# SNES.net
KiCad netlist of a schematic drawn in EAGLE
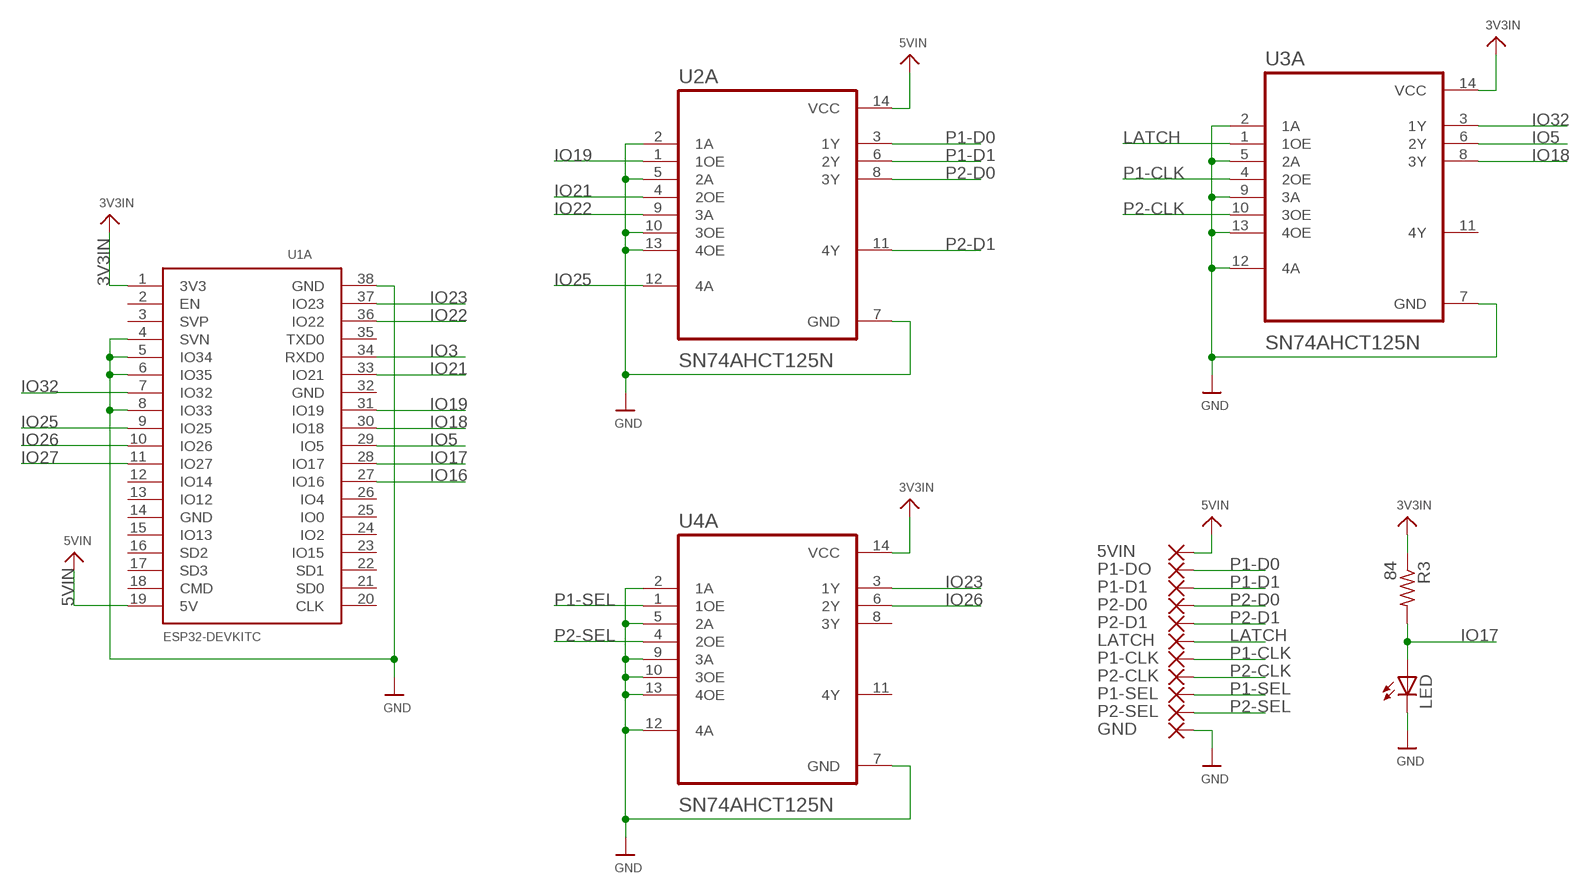
[diagram p0: schematic, sheet 1]

(export (version "E")
  (design (tool "Eeschema 10.0.6"))
  (components
    (comp (ref "5VIN")
      (value "SMD5")
      (footprint "eagle-import:SMD2,54-5,08")
      (libsource (lib "eagle-import") (part "SMD5"))
    )
    (comp (ref "GND")
      (value "SMD5")
      (footprint "eagle-import:SMD2,54-5,08")
      (libsource (lib "eagle-import") (part "SMD5"))
    )
    (comp (ref "LATCH")
      (value "SMD5")
      (footprint "eagle-import:SMD2,54-5,08")
      (libsource (lib "eagle-import") (part "SMD5"))
    )
    (comp (ref "LED")
      (value "LEDCHIPLED_1206")
      (footprint "eagle-import:CHIPLED_1206")
      (libsource (lib "eagle-import") (part "LEDCHIPLED_1206"))
    )
    (comp (ref "P1-CLK")
      (value "SMD5")
      (footprint "eagle-import:SMD2,54-5,08")
      (libsource (lib "eagle-import") (part "SMD5"))
    )
    (comp (ref "P1-D1")
      (value "SMD5")
      (footprint "eagle-import:SMD2,54-5,08")
      (libsource (lib "eagle-import") (part "SMD5"))
    )
    (comp (ref "P1-DO")
      (value "SMD5")
      (footprint "eagle-import:SMD2,54-5,08")
      (libsource (lib "eagle-import") (part "SMD5"))
    )
    (comp (ref "P1-SEL")
      (value "SMD5")
      (footprint "eagle-import:SMD2,54-5,08")
      (libsource (lib "eagle-import") (part "SMD5"))
    )
    (comp (ref "P2-CLK")
      (value "SMD5")
      (footprint "eagle-import:SMD2,54-5,08")
      (libsource (lib "eagle-import") (part "SMD5"))
    )
    (comp (ref "P2-D0")
      (value "SMD5")
      (footprint "eagle-import:SMD2,54-5,08")
      (libsource (lib "eagle-import") (part "SMD5"))
    )
    (comp (ref "P2-D1")
      (value "SMD5")
      (footprint "eagle-import:SMD2,54-5,08")
      (libsource (lib "eagle-import") (part "SMD5"))
    )
    (comp (ref "P2-SEL")
      (value "SMD5")
      (footprint "eagle-import:SMD2,54-5,08")
      (libsource (lib "eagle-import") (part "SMD5"))
    )
    (comp (ref "R3")
      (value "84")
      (footprint "eagle-import:R1206")
      (libsource (lib "eagle-import") (part "R-US_R1206"))
    )
    (comp (ref "U1A")
      (value "ESP32DEVKITC")
      (footprint "eagle-import:ESP32-DEVKITC")
      (libsource (lib "eagle-import") (part "ESP32DEVKITC"))
    )
    (comp (ref "U2A")
      (value "SN74AHCT125N")
      (footprint "eagle-import:DIP794W45P254L1969H508Q14")
      (fields (field (name "MF") "Texas Instruments"))
      (libsource (lib "eagle-import") (part "SN74AHCT125N"))
    )
    (comp (ref "U3A")
      (value "SN74AHCT125N")
      (footprint "eagle-import:DIP794W45P254L1969H508Q14")
      (fields (field (name "MF") "Texas Instruments"))
      (libsource (lib "eagle-import") (part "SN74AHCT125N"))
    )
    (comp (ref "U4A")
      (value "SN74AHCT125N")
      (footprint "eagle-import:DIP794W45P254L1969H508Q14")
      (fields (field (name "MF") "Texas Instruments"))
      (libsource (lib "eagle-import") (part "SN74AHCT125N"))
    )
  )
  (nets
    (net (code "1") (name "/IO3") (class "Default")
      (node (ref "U1A") (pin "34") (pinfunction "RXD0_34") (pintype "bidirectional"))
    )
    (net (code "2") (name "/IO5") (class "Default")
      (node (ref "U1A") (pin "29") (pinfunction "IO5_29") (pintype "bidirectional"))
      (node (ref "U3A") (pin "6") (pinfunction "2Y_6") (pintype "output"))
    )
    (net (code "3") (name "/IO16") (class "Default")
      (node (ref "U1A") (pin "27") (pinfunction "IO16_27") (pintype "bidirectional"))
    )
    (net (code "4") (name "/IO17") (class "Default")
      (node (ref "LED") (pin "A") (pinfunction "A_A") (pintype "passive"))
      (node (ref "R3") (pin "2") (pinfunction "2_2") (pintype "passive"))
      (node (ref "U1A") (pin "28") (pinfunction "IO17_28") (pintype "bidirectional"))
    )
    (net (code "5") (name "/IO18") (class "Default")
      (node (ref "U1A") (pin "30") (pinfunction "IO18_30") (pintype "bidirectional"))
      (node (ref "U3A") (pin "8") (pinfunction "3Y_8") (pintype "output"))
    )
    (net (code "6") (name "/IO19") (class "Default")
      (node (ref "U1A") (pin "31") (pinfunction "IO19_31") (pintype "bidirectional"))
      (node (ref "U2A") (pin "1") (pinfunction "1OE_1") (pintype "input"))
    )
    (net (code "7") (name "/IO21") (class "Default")
      (node (ref "U1A") (pin "33") (pinfunction "IO21_33") (pintype "bidirectional"))
      (node (ref "U2A") (pin "4") (pinfunction "2OE_4") (pintype "input"))
    )
    (net (code "8") (name "/IO22") (class "Default")
      (node (ref "U1A") (pin "36") (pinfunction "IO22_36") (pintype "bidirectional"))
      (node (ref "U2A") (pin "9") (pinfunction "3A_9") (pintype "input"))
    )
    (net (code "9") (name "/IO23") (class "Default")
      (node (ref "U1A") (pin "37") (pinfunction "IO23_37") (pintype "bidirectional"))
      (node (ref "U4A") (pin "3") (pinfunction "1Y_3") (pintype "output"))
    )
    (net (code "10") (name "/IO25") (class "Default")
      (node (ref "U1A") (pin "9") (pinfunction "IO25_9") (pintype "bidirectional"))
      (node (ref "U2A") (pin "12") (pinfunction "4A_12") (pintype "bidirectional"))
    )
    (net (code "11") (name "/IO26") (class "Default")
      (node (ref "U1A") (pin "10") (pinfunction "IO26_10") (pintype "bidirectional"))
      (node (ref "U4A") (pin "6") (pinfunction "2Y_6") (pintype "output"))
    )
    (net (code "12") (name "/IO27") (class "Default")
      (node (ref "U1A") (pin "11") (pinfunction "IO27_11") (pintype "bidirectional"))
    )
    (net (code "13") (name "/IO32") (class "Default")
      (node (ref "U1A") (pin "7") (pinfunction "IO32_7") (pintype "bidirectional"))
      (node (ref "U3A") (pin "3") (pinfunction "1Y_3") (pintype "output"))
    )
    (net (code "14") (name "/LATCH") (class "Default")
      (node (ref "LATCH") (pin "1") (pinfunction "P_1") (pintype "passive"))
      (node (ref "U3A") (pin "1") (pinfunction "1OE_1") (pintype "input"))
    )
    (net (code "15") (name "/P1-CLK") (class "Default")
      (node (ref "P1-CLK") (pin "1") (pinfunction "P_1") (pintype "passive"))
      (node (ref "U3A") (pin "4") (pinfunction "2OE_4") (pintype "input"))
    )
    (net (code "16") (name "/P1-D0") (class "Default")
      (node (ref "P1-DO") (pin "1") (pinfunction "P_1") (pintype "passive"))
      (node (ref "U2A") (pin "3") (pinfunction "1Y_3") (pintype "output"))
    )
    (net (code "17") (name "/P1-D1") (class "Default")
      (node (ref "P1-D1") (pin "1") (pinfunction "P_1") (pintype "passive"))
      (node (ref "U2A") (pin "6") (pinfunction "2Y_6") (pintype "output"))
    )
    (net (code "18") (name "/P1-SEL") (class "Default")
      (node (ref "P1-SEL") (pin "1") (pinfunction "P_1") (pintype "passive"))
      (node (ref "U4A") (pin "1") (pinfunction "1OE_1") (pintype "input"))
    )
    (net (code "19") (name "/P2-CLK") (class "Default")
      (node (ref "P2-CLK") (pin "1") (pinfunction "P_1") (pintype "passive"))
      (node (ref "U3A") (pin "10") (pinfunction "3OE_10") (pintype "input"))
    )
    (net (code "20") (name "/P2-D0") (class "Default")
      (node (ref "P2-D0") (pin "1") (pinfunction "P_1") (pintype "passive"))
      (node (ref "U2A") (pin "8") (pinfunction "3Y_8") (pintype "output"))
    )
    (net (code "21") (name "/P2-D1") (class "Default")
      (node (ref "P2-D1") (pin "1") (pinfunction "P_1") (pintype "passive"))
      (node (ref "U2A") (pin "11") (pinfunction "4Y_11") (pintype "output"))
    )
    (net (code "22") (name "/P2-SEL") (class "Default")
      (node (ref "P2-SEL") (pin "1") (pinfunction "P_1") (pintype "passive"))
      (node (ref "U4A") (pin "4") (pinfunction "2OE_4") (pintype "input"))
    )
    (net (code "23") (name "3V3IN") (class "Default")
      (node (ref "R3") (pin "1") (pinfunction "1_1") (pintype "passive"))
      (node (ref "U1A") (pin "1") (pinfunction "3V3_1") (pintype "bidirectional"))
      (node (ref "U3A") (pin "14") (pinfunction "VCC_14") (pintype "power_in"))
      (node (ref "U4A") (pin "14") (pinfunction "VCC_14") (pintype "power_in"))
    )
    (net (code "24") (name "5VIN") (class "Default")
      (node (ref "5VIN") (pin "1") (pinfunction "P_1") (pintype "passive"))
      (node (ref "U1A") (pin "19") (pinfunction "5V_19") (pintype "bidirectional"))
      (node (ref "U2A") (pin "14") (pinfunction "VCC_14") (pintype "power_in"))
    )
    (net (code "25") (name "GND") (class "Default")
      (node (ref "GND") (pin "1") (pinfunction "P_1") (pintype "passive"))
      (node (ref "LED") (pin "C") (pinfunction "C_C") (pintype "passive"))
      (node (ref "U1A") (pin "38") (pinfunction "GND_38") (pintype "bidirectional"))
      (node (ref "U1A") (pin "4") (pinfunction "SVN_4") (pintype "bidirectional"))
      (node (ref "U1A") (pin "5") (pinfunction "IO34_5") (pintype "bidirectional"))
      (node (ref "U1A") (pin "6") (pinfunction "IO35_6") (pintype "bidirectional"))
      (node (ref "U1A") (pin "8") (pinfunction "IO33_8") (pintype "bidirectional"))
      (node (ref "U2A") (pin "10") (pinfunction "3OE_10") (pintype "input"))
      (node (ref "U2A") (pin "13") (pinfunction "4OE_13") (pintype "input"))
      (node (ref "U2A") (pin "2") (pinfunction "1A_2") (pintype "input"))
      (node (ref "U2A") (pin "5") (pinfunction "2A_5") (pintype "input"))
      (node (ref "U2A") (pin "7") (pinfunction "GND_7") (pintype "power_in"))
      (node (ref "U3A") (pin "12") (pinfunction "4A_12") (pintype "bidirectional"))
      (node (ref "U3A") (pin "13") (pinfunction "4OE_13") (pintype "input"))
      (node (ref "U3A") (pin "2") (pinfunction "1A_2") (pintype "input"))
      (node (ref "U3A") (pin "5") (pinfunction "2A_5") (pintype "input"))
      (node (ref "U3A") (pin "7") (pinfunction "GND_7") (pintype "power_in"))
      (node (ref "U3A") (pin "9") (pinfunction "3A_9") (pintype "input"))
      (node (ref "U4A") (pin "10") (pinfunction "3OE_10") (pintype "input"))
      (node (ref "U4A") (pin "12") (pinfunction "4A_12") (pintype "bidirectional"))
      (node (ref "U4A") (pin "13") (pinfunction "4OE_13") (pintype "input"))
      (node (ref "U4A") (pin "2") (pinfunction "1A_2") (pintype "input"))
      (node (ref "U4A") (pin "5") (pinfunction "2A_5") (pintype "input"))
      (node (ref "U4A") (pin "7") (pinfunction "GND_7") (pintype "power_in"))
      (node (ref "U4A") (pin "9") (pinfunction "3A_9") (pintype "input"))
    )
    (net (code "26") (name "unconnected-(U1A-CLK-Pad20)") (class "Default")
      (node (ref "U1A") (pin "20") (pinfunction "CLK_20") (pintype "bidirectional"))
    )
    (net (code "27") (name "unconnected-(U1A-CMD-Pad18)") (class "Default")
      (node (ref "U1A") (pin "18") (pinfunction "CMD_18") (pintype "bidirectional"))
    )
    (net (code "28") (name "unconnected-(U1A-EN-Pad2)") (class "Default")
      (node (ref "U1A") (pin "2") (pinfunction "EN_2") (pintype "bidirectional"))
    )
    (net (code "29") (name "unconnected-(U1A-GND-Pad14)") (class "Default")
      (node (ref "U1A") (pin "14") (pinfunction "GND_14") (pintype "bidirectional"))
    )
    (net (code "30") (name "unconnected-(U1A-GND-Pad32)") (class "Default")
      (node (ref "U1A") (pin "32") (pinfunction "GND_32") (pintype "bidirectional"))
    )
    (net (code "31") (name "unconnected-(U1A-IO0-Pad25)") (class "Default")
      (node (ref "U1A") (pin "25") (pinfunction "IO0_25") (pintype "bidirectional"))
    )
    (net (code "32") (name "unconnected-(U1A-IO2-Pad24)") (class "Default")
      (node (ref "U1A") (pin "24") (pinfunction "IO2_24") (pintype "bidirectional"))
    )
    (net (code "33") (name "unconnected-(U1A-IO4-Pad26)") (class "Default")
      (node (ref "U1A") (pin "26") (pinfunction "IO4_26") (pintype "bidirectional"))
    )
    (net (code "34") (name "unconnected-(U1A-IO12-Pad13)") (class "Default")
      (node (ref "U1A") (pin "13") (pinfunction "IO12_13") (pintype "bidirectional"))
    )
    (net (code "35") (name "unconnected-(U1A-IO13-Pad15)") (class "Default")
      (node (ref "U1A") (pin "15") (pinfunction "IO13_15") (pintype "bidirectional"))
    )
    (net (code "36") (name "unconnected-(U1A-IO14-Pad12)") (class "Default")
      (node (ref "U1A") (pin "12") (pinfunction "IO14_12") (pintype "bidirectional"))
    )
    (net (code "37") (name "unconnected-(U1A-IO15-Pad23)") (class "Default")
      (node (ref "U1A") (pin "23") (pinfunction "IO15_23") (pintype "bidirectional"))
    )
    (net (code "38") (name "unconnected-(U1A-SD0-Pad21)") (class "Default")
      (node (ref "U1A") (pin "21") (pinfunction "SD0_21") (pintype "bidirectional"))
    )
    (net (code "39") (name "unconnected-(U1A-SD1-Pad22)") (class "Default")
      (node (ref "U1A") (pin "22") (pinfunction "SD1_22") (pintype "bidirectional"))
    )
    (net (code "40") (name "unconnected-(U1A-SD2-Pad16)") (class "Default")
      (node (ref "U1A") (pin "16") (pinfunction "SD2_16") (pintype "bidirectional"))
    )
    (net (code "41") (name "unconnected-(U1A-SD3-Pad17)") (class "Default")
      (node (ref "U1A") (pin "17") (pinfunction "SD3_17") (pintype "bidirectional"))
    )
    (net (code "42") (name "unconnected-(U1A-SVP-Pad3)") (class "Default")
      (node (ref "U1A") (pin "3") (pinfunction "SVP_3") (pintype "bidirectional"))
    )
    (net (code "43") (name "unconnected-(U1A-TXD0-Pad35)") (class "Default")
      (node (ref "U1A") (pin "35") (pinfunction "TXD0_35") (pintype "bidirectional"))
    )
    (net (code "44") (name "unconnected-(U3A-4Y-Pad11)") (class "Default")
      (node (ref "U3A") (pin "11") (pinfunction "4Y_11") (pintype "output"))
    )
    (net (code "45") (name "unconnected-(U4A-3Y-Pad8)") (class "Default")
      (node (ref "U4A") (pin "8") (pinfunction "3Y_8") (pintype "output"))
    )
    (net (code "46") (name "unconnected-(U4A-4Y-Pad11)") (class "Default")
      (node (ref "U4A") (pin "11") (pinfunction "4Y_11") (pintype "output"))
    )
  )
)
